# ButtonFiltr.net
KiCad netlist of a schematic drawn in Altium Designer
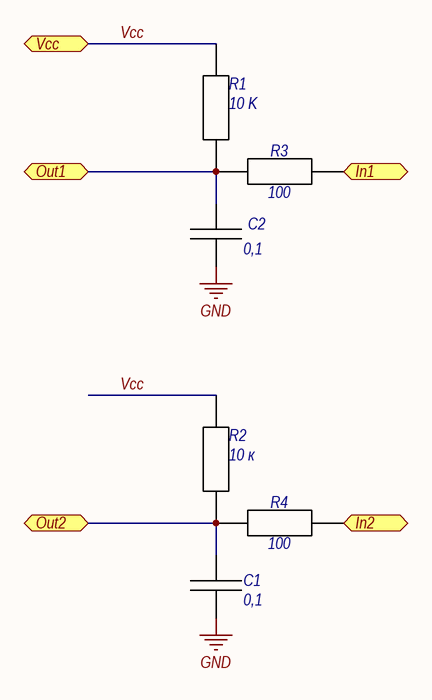
[diagram p0: ButtonFiltr.SchDoc]

(export (version "E")
  (design (tool "Eeschema 10.0.6"))
  (components
    (comp (ref "C1")
      (value "Конденсаторы керамические")
      (footprint "C0603_autoMount")
      (fields
        (field (name "PART NUMBER") "Чип. керам. 0603 0,1 мкФ 50 В +/-10% X7R CC0603KKX7R9BB104 \"Yageo\"")
        (field (name "MANUFACTURER") "\"Yageo\"")
        (field (name "MANUFACTURERPARTNUMBER") "CC0603KKX7R9BB104")
        (field (name "VALUE SCH") "0,1")
      )
      (libsource (lib "Library") (part "Конденсаторы керамические"))
    )
    (comp (ref "C2")
      (value "Конденсаторы керамические")
      (footprint "C0603_autoMount")
      (fields
        (field (name "PART NUMBER") "Чип. керам. 0603 0,1 мкФ 50 В +/-10% X7R CC0603KKX7R9BB104 \"Yageo\"")
        (field (name "MANUFACTURER") "\"Yageo\"")
        (field (name "MANUFACTURERPARTNUMBER") "CC0603KKX7R9BB104")
        (field (name "VALUE SCH") "0,1")
      )
      (libsource (lib "Library") (part "Конденсаторы керамические"))
    )
    (comp (ref "R1")
      (value "Resistor")
      (footprint "R0603_autoMount")
      (fields
        (field (name "PART NUMBER") "Чип рез. 0603 10 кОм  +/-1% RC0603FR-0710KL \"Yageo\"")
        (field (name "MANUFACTURER") "\"Yageo\"")
        (field (name "MANUFACTURERPARTNUMBER") "RC0603FR-0710KL")
        (field (name "VALUE EURO") "10 K")
      )
      (libsource (lib "") (part "Resistor_1"))
    )
    (comp (ref "R2")
      (value "Resistor")
      (footprint "R0603_autoMount")
      (fields
        (field (name "PART NUMBER") "Чип рез. 0603 10 кОм  +/-1% RC0603FR-0710KL \"Yageo\"")
        (field (name "MANUFACTURER") "\"Yageo\"")
        (field (name "MANUFACTURERPARTNUMBER") "RC0603FR-0710KL")
        (field (name "VALUE SСH") "10 к")
      )
      (libsource (lib "") (part "Resistor_1"))
    )
    (comp (ref "R3")
      (value "Resistor")
      (footprint "R0603_autoMount")
      (fields
        (field (name "PART NUMBER") "Чип рез. 0603 100 Ом  +/-1% RC0603FR-07100RL \"Yageo\"")
        (field (name "MANUFACTURER") "\"Yageo\"")
        (field (name "MANUFACTURERPARTNUMBER") "RC0603FR-07100RL")
        (field (name "VALUE SСH") "100")
      )
      (libsource (lib "Library") (part "Resistor"))
    )
    (comp (ref "R4")
      (value "Resistor")
      (footprint "R0603_autoMount")
      (fields
        (field (name "PART NUMBER") "Чип рез. 0603 100 Ом  +/-1% RC0603FR-07100RL \"Yageo\"")
        (field (name "MANUFACTURER") "\"Yageo\"")
        (field (name "MANUFACTURERPARTNUMBER") "RC0603FR-07100RL")
        (field (name "VALUE SСH") "100")
      )
      (libsource (lib "Library") (part "Resistor"))
    )
  )
  (nets
    (net (code "1") (name "/In1") (class "Default")
      (node (ref "R3") (pin "1") (pinfunction "1_1") (pintype "passive"))
    )
    (net (code "2") (name "/In2") (class "Default")
      (node (ref "R4") (pin "1") (pinfunction "1_1") (pintype "passive"))
    )
    (net (code "3") (name "/Out1") (class "Default")
      (node (ref "C2") (pin "2") (pinfunction "2_2") (pintype "passive"))
      (node (ref "R1") (pin "2") (pinfunction "2_2") (pintype "passive"))
      (node (ref "R3") (pin "2") (pinfunction "2_2") (pintype "passive"))
    )
    (net (code "4") (name "/Out2") (class "Default")
      (node (ref "C1") (pin "2") (pinfunction "2_2") (pintype "passive"))
      (node (ref "R2") (pin "2") (pinfunction "2_2") (pintype "passive"))
      (node (ref "R4") (pin "2") (pinfunction "2_2") (pintype "passive"))
    )
    (net (code "5") (name "/Vcc") (class "Default")
      (node (ref "R1") (pin "1") (pinfunction "1_1") (pintype "passive"))
      (node (ref "R2") (pin "1") (pinfunction "1_1") (pintype "passive"))
    )
    (net (code "6") (name "GND") (class "Default")
      (node (ref "C1") (pin "1") (pinfunction "1_1") (pintype "passive"))
      (node (ref "C2") (pin "1") (pinfunction "1_1") (pintype "passive"))
    )
  )
)
